# Power.net
KiCad netlist of a schematic drawn in Altium Designer
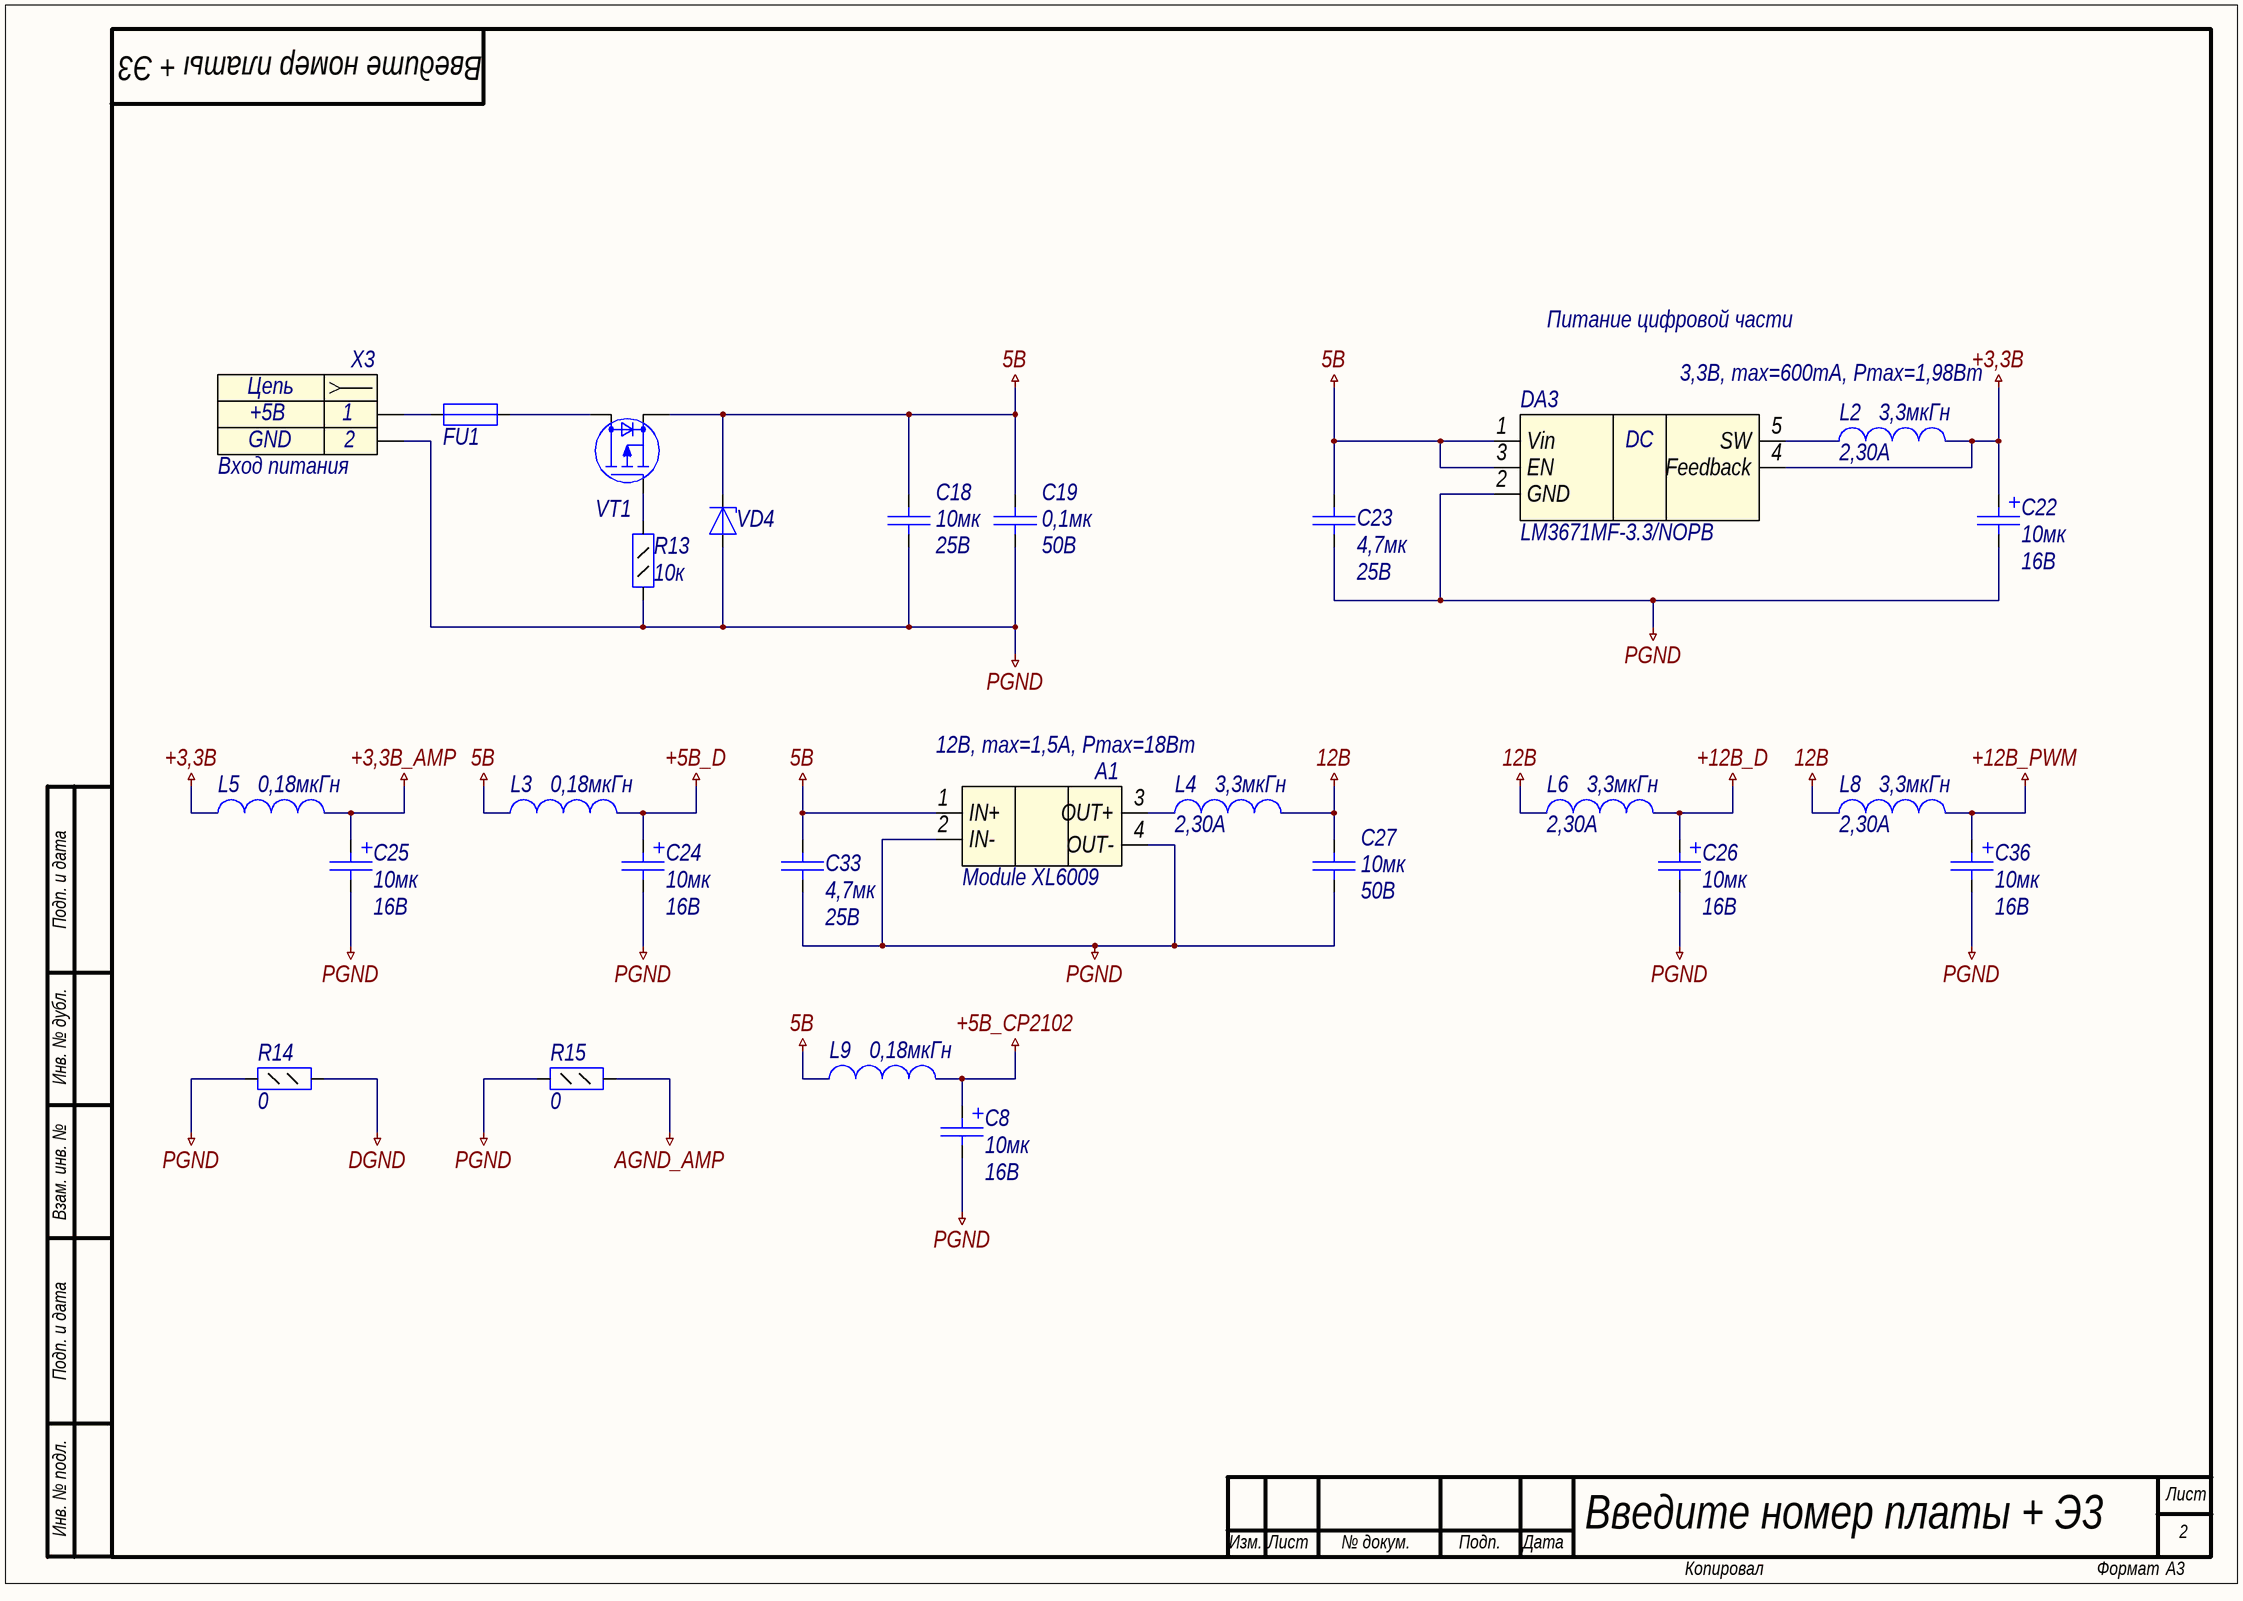
[diagram p0: Power.SchDoc]

(export (version "E")
  (design (tool "Eeschema 10.0.6"))
  (components
    (comp (ref "A1")
      (value "Module XL6009")
      (footprint "Module XL6009")
      (description "DC-DC step-up converter for 5/32-V to 5/35-V")
      (libsource (lib "MOP44") (part "Module XL6009"))
    )
    (comp (ref "C8")
      (value "10мк")
      (footprint "TANTAL CASE A")
      (description "Конденсатор полярный")
      (fields
        (field (name "VOLTAGE") "16В")
        (field (name "PART NUMBER") "293D106X9016A2TE3")
        (field (name "Comment") "Capacitor_pol")
      )
      (libsource (lib "MOP44") (part "Capacitor_pol"))
    )
    (comp (ref "C18")
      (value "10мк")
      (footprint "C1206")
      (description "Конденсатор")
      (fields
        (field (name "VOLTAGE") "25В")
        (field (name "PART NUMBER") "GRM31CR71E106KA12L*")
        (field (name "Comment") "Capacitor")
      )
      (libsource (lib "MOP44") (part "Capacitor"))
    )
    (comp (ref "C19")
      (value "0,1мк")
      (footprint "C0805")
      (description "Конденсатор")
      (fields
        (field (name "VOLTAGE") "50В")
        (field (name "PART NUMBER") "GRM21BR71H104KA01L ")
        (field (name "Comment") "Capacitor")
      )
      (libsource (lib "MOP44") (part "Capacitor"))
    )
    (comp (ref "C22")
      (value "10мк")
      (footprint "TANTAL CASE A")
      (description "Конденсатор полярный")
      (fields
        (field (name "VOLTAGE") "16В")
        (field (name "PART NUMBER") "293D106X9016A2TE3")
        (field (name "Comment") "Capacitor_pol")
      )
      (libsource (lib "MOP44") (part "Capacitor_pol"))
    )
    (comp (ref "C23")
      (value "4,7мк")
      (footprint "C0805")
      (description "Конденсатор")
      (fields
        (field (name "VOLTAGE") "25B")
        (field (name "PART NUMBER") "GRM21BR61E475KA12L")
        (field (name "Comment") "Capacitor")
      )
      (libsource (lib "MOP44") (part "Capacitor"))
    )
    (comp (ref "C24")
      (value "10мк")
      (footprint "TANTAL CASE A")
      (description "Конденсатор полярный")
      (fields
        (field (name "VOLTAGE") "16В")
        (field (name "PART NUMBER") "293D106X9016A2TE3")
        (field (name "Comment") "Capacitor_pol")
      )
      (libsource (lib "MOP44") (part "Capacitor_pol"))
    )
    (comp (ref "C25")
      (value "10мк")
      (footprint "TANTAL CASE A")
      (description "Конденсатор полярный")
      (fields
        (field (name "VOLTAGE") "16В")
        (field (name "PART NUMBER") "293D106X9016A2TE3")
        (field (name "Comment") "Capacitor_pol")
      )
      (libsource (lib "MOP44") (part "Capacitor_pol"))
    )
    (comp (ref "C26")
      (value "10мк")
      (footprint "TANTAL CASE A")
      (description "Конденсатор полярный")
      (fields
        (field (name "VOLTAGE") "16В")
        (field (name "PART NUMBER") "293D106X9016A2TE3")
        (field (name "Comment") "Capacitor_pol")
      )
      (libsource (lib "MOP44") (part "Capacitor_pol"))
    )
    (comp (ref "C27")
      (value "10мк")
      (footprint "C1210")
      (description "Конденсатор")
      (fields
        (field (name "VOLTAGE") "50В")
        (field (name "PART NUMBER") "GRM32ER71H106K")
        (field (name "Comment") "Capacitor")
      )
      (libsource (lib "MOP44") (part "Capacitor"))
    )
    (comp (ref "C33")
      (value "4,7мк")
      (footprint "C0805")
      (description "Конденсатор")
      (fields
        (field (name "VOLTAGE") "25B")
        (field (name "PART NUMBER") "GRM21BR61E475KA12L")
        (field (name "Comment") "Capacitor")
      )
      (libsource (lib "MOP44") (part "Capacitor"))
    )
    (comp (ref "C36")
      (value "10мк")
      (footprint "TANTAL CASE A")
      (description "Конденсатор полярный")
      (fields
        (field (name "VOLTAGE") "16В")
        (field (name "PART NUMBER") "293D106X9016A2TE3")
        (field (name "Comment") "Capacitor_pol")
      )
      (libsource (lib "MOP44") (part "Capacitor_pol"))
    )
    (comp (ref "DA3")
      (value "LM3671MF")
      (footprint "SOT23-5")
      (description "Step-Down DC-DC Converter")
      (fields
        (field (name "PART NUMBER") "LM3671MF-3.3/NOPB")
        (field (name "MANUFACTURER") "Texas Instruments")
      )
      (libsource (lib "MOP44") (part "LM3671MF"))
    )
    (comp (ref "FU1")
      (value "Fuse")
      (footprint "FUSE812")
      (description "Предохранитель")
      (fields (field (name "PART NUMBER") "MF-MSMF075"))
      (libsource (lib "MOP44") (part "Fuse"))
    )
    (comp (ref "L2")
      (value "3,3мкГн")
      (footprint "SRR0604")
      (description "EMI Suppression Filter")
      (fields
        (field (name "RATED CURRENT") "2,30А")
        (field (name "PART NUMBER") "SRR0604-3R3ML")
        (field (name "Comment") "Inductor")
      )
      (libsource (lib "MOP44") (part "Inductor"))
    )
    (comp (ref "L3")
      (value "0,18мкГн")
      (footprint "L0805")
      (description "EMI Suppression Filter")
      (fields (field (name "PART NUMBER") "CM201212-R18KL") (field (name "Comment") "Inductor"))
      (libsource (lib "MOP44") (part "Inductor"))
    )
    (comp (ref "L4")
      (value "3,3мкГн")
      (footprint "SRR0604")
      (description "EMI Suppression Filter")
      (fields
        (field (name "RATED CURRENT") "2,30А")
        (field (name "PART NUMBER") "SRR0604-3R3ML")
        (field (name "Comment") "Inductor")
      )
      (libsource (lib "MOP44") (part "Inductor"))
    )
    (comp (ref "L5")
      (value "0,18мкГн")
      (footprint "L0805")
      (description "EMI Suppression Filter")
      (fields (field (name "PART NUMBER") "CM201212-R18KL") (field (name "Comment") "Inductor"))
      (libsource (lib "MOP44") (part "Inductor"))
    )
    (comp (ref "L6")
      (value "3,3мкГн")
      (footprint "SRR0604")
      (description "EMI Suppression Filter")
      (fields
        (field (name "RATED CURRENT") "2,30А")
        (field (name "PART NUMBER") "SRR0604-3R3ML")
        (field (name "Comment") "Inductor")
      )
      (libsource (lib "MOP44") (part "Inductor"))
    )
    (comp (ref "L8")
      (value "3,3мкГн")
      (footprint "SRR0604")
      (description "EMI Suppression Filter")
      (fields
        (field (name "RATED CURRENT") "2,30А")
        (field (name "PART NUMBER") "SRR0604-3R3ML")
        (field (name "Comment") "Inductor")
      )
      (libsource (lib "MOP44") (part "Inductor"))
    )
    (comp (ref "L9")
      (value "0,18мкГн")
      (footprint "L0805")
      (description "EMI Suppression Filter")
      (fields (field (name "PART NUMBER") "CM201212-R18KL") (field (name "Comment") "Inductor"))
      (libsource (lib "MOP44") (part "Inductor"))
    )
    (comp (ref "R13")
      (value "10к")
      (footprint "R0805")
      (description "Резистор")
      (fields (field (name "PART NUMBER") "RC0805FR-0710KL") (field (name "POWER") "0,125Вт"))
      (libsource (lib "") (part "Resistor_0,125Вт_1"))
    )
    (comp (ref "R14")
      (value "0")
      (footprint "R0805")
      (description "Резистор")
      (fields (field (name "PART NUMBER") "RC0805FR-070RL") (field (name "POWER") "0,125Вт"))
      (libsource (lib "MOP44") (part "Resistor_0,125Вт"))
    )
    (comp (ref "R15")
      (value "0")
      (footprint "R0805")
      (description "Резистор")
      (fields (field (name "PART NUMBER") "RC0805FR-070RL") (field (name "POWER") "0,125Вт"))
      (libsource (lib "MOP44") (part "Resistor_0,125Вт"))
    )
    (comp (ref "VD4")
      (value "DiodeZener")
      (footprint "SMA")
      (description "Cтабилитрон (лавинный выпрямительный диод) односторонний")
      (fields (field (name "PART NUMBER") "SMAJ5.0A"))
      (libsource (lib "MOP44") (part "DiodeZener"))
    )
    (comp (ref "VT1")
      (value "P-MOSFET")
      (footprint "SOT23-3")
      (description "N-MOSFET")
      (fields
        (field (name "PART NUMBER") "IRLML6401TRPBF")
        (field (name "MANUFACTURER") "International Rectifier")
      )
      (libsource (lib "MOP44") (part "P-MOSFET"))
    )
    (comp (ref "X3")
      (value "Вход питания")
      (footprint "CWF-2R")
      (description "Разъем - 2 конт. розетка")
      (fields (field (name "PART NUMBER") "DS1069-2 MR-A"))
      (libsource (lib "MOP44") (part "Header_2_sct"))
    )
  )
  (nets
    (net (code "1") (name "+3,3В") (class "Default")
      (node (ref "C22") (pin "1") (pinfunction "1_1") (pintype "passive"))
      (node (ref "DA3") (pin "4") (pinfunction "Feedback_4") (pintype "power_in"))
      (node (ref "L2") (pin "2") (pinfunction "2_2") (pintype "passive"))
      (node (ref "L5") (pin "1") (pinfunction "1_1") (pintype "passive"))
    )
    (net (code "2") (name "+3,3В_AMP") (class "Default")
      (node (ref "C25") (pin "1") (pinfunction "1_1") (pintype "passive"))
      (node (ref "L5") (pin "2") (pinfunction "2_2") (pintype "passive"))
    )
    (net (code "3") (name "+5B_CP2102") (class "Default")
      (node (ref "C8") (pin "1") (pinfunction "1_1") (pintype "passive"))
      (node (ref "L9") (pin "2") (pinfunction "2_2") (pintype "passive"))
    )
    (net (code "4") (name "+5B_D") (class "Default")
      (node (ref "C24") (pin "1") (pinfunction "1_1") (pintype "passive"))
      (node (ref "L3") (pin "2") (pinfunction "2_2") (pintype "passive"))
    )
    (net (code "5") (name "+12В_D") (class "Default")
      (node (ref "C26") (pin "1") (pinfunction "1_1") (pintype "passive"))
      (node (ref "L6") (pin "2") (pinfunction "2_2") (pintype "passive"))
    )
    (net (code "6") (name "+12В_PWM") (class "Default")
      (node (ref "C36") (pin "1") (pinfunction "1_1") (pintype "passive"))
      (node (ref "L8") (pin "2") (pinfunction "2_2") (pintype "passive"))
    )
    (net (code "7") (name "5B") (class "Default")
      (node (ref "A1") (pin "1") (pinfunction "IN+_1") (pintype "power_in"))
      (node (ref "C18") (pin "2") (pinfunction "2_2") (pintype "passive"))
      (node (ref "C19") (pin "2") (pinfunction "2_2") (pintype "passive"))
      (node (ref "C23") (pin "2") (pinfunction "2_2") (pintype "passive"))
      (node (ref "C33") (pin "2") (pinfunction "2_2") (pintype "passive"))
      (node (ref "DA3") (pin "1") (pinfunction "Vin_1") (pintype "power_in"))
      (node (ref "DA3") (pin "3") (pinfunction "EN_3") (pintype "power_in"))
      (node (ref "L3") (pin "1") (pinfunction "1_1") (pintype "passive"))
      (node (ref "L9") (pin "1") (pinfunction "1_1") (pintype "passive"))
      (node (ref "VD4") (pin "1") (pinfunction "K_1") (pintype "passive"))
      (node (ref "VT1") (pin "3") (pinfunction "S_3") (pintype "passive"))
    )
    (net (code "8") (name "12В") (class "Default")
      (node (ref "C27") (pin "2") (pinfunction "2_2") (pintype "passive"))
      (node (ref "L4") (pin "2") (pinfunction "2_2") (pintype "passive"))
      (node (ref "L6") (pin "1") (pinfunction "1_1") (pintype "passive"))
      (node (ref "L8") (pin "1") (pinfunction "1_1") (pintype "passive"))
    )
    (net (code "9") (name "AGND_AMP") (class "Default")
      (node (ref "R15") (pin "2") (pinfunction "2_2") (pintype "passive"))
    )
    (net (code "10") (name "DGND") (class "Default")
      (node (ref "R14") (pin "2") (pinfunction "2_2") (pintype "passive"))
    )
    (net (code "11") (name "Net-(A1-OUT+)") (class "Default")
      (node (ref "A1") (pin "3") (pinfunction "OUT+_3") (pintype "power_in"))
      (node (ref "L4") (pin "1") (pinfunction "1_1") (pintype "passive"))
    )
    (net (code "12") (name "Net-(DA3-SW)") (class "Default")
      (node (ref "DA3") (pin "5") (pinfunction "SW_5") (pintype "power_in"))
      (node (ref "L2") (pin "1") (pinfunction "1_1") (pintype "passive"))
    )
    (net (code "13") (name "Net-(FU1-Pad1)") (class "Default")
      (node (ref "FU1") (pin "1") (pinfunction "1_1") (pintype "passive"))
      (node (ref "X3") (pin "1") (pinfunction "1_1") (pintype "passive"))
    )
    (net (code "14") (name "Net-(VT1-D)") (class "Default")
      (node (ref "FU1") (pin "2") (pinfunction "2_2") (pintype "passive"))
      (node (ref "VT1") (pin "2") (pinfunction "D_2") (pintype "passive"))
    )
    (net (code "15") (name "Net-(VT1-G)") (class "Default")
      (node (ref "R13") (pin "2") (pinfunction "2_2") (pintype "passive"))
      (node (ref "VT1") (pin "1") (pinfunction "G_1") (pintype "passive"))
    )
    (net (code "16") (name "PGND") (class "Default")
      (node (ref "A1") (pin "2") (pinfunction "IN-_2") (pintype "power_in"))
      (node (ref "A1") (pin "4") (pinfunction "OUT-_4") (pintype "power_in"))
      (node (ref "C18") (pin "1") (pinfunction "1_1") (pintype "passive"))
      (node (ref "C19") (pin "1") (pinfunction "1_1") (pintype "passive"))
      (node (ref "C22") (pin "2") (pinfunction "2_2") (pintype "passive"))
      (node (ref "C23") (pin "1") (pinfunction "1_1") (pintype "passive"))
      (node (ref "C24") (pin "2") (pinfunction "2_2") (pintype "passive"))
      (node (ref "C25") (pin "2") (pinfunction "2_2") (pintype "passive"))
      (node (ref "C26") (pin "2") (pinfunction "2_2") (pintype "passive"))
      (node (ref "C27") (pin "1") (pinfunction "1_1") (pintype "passive"))
      (node (ref "C33") (pin "1") (pinfunction "1_1") (pintype "passive"))
      (node (ref "C36") (pin "2") (pinfunction "2_2") (pintype "passive"))
      (node (ref "C8") (pin "2") (pinfunction "2_2") (pintype "passive"))
      (node (ref "DA3") (pin "2") (pinfunction "GND_2") (pintype "power_in"))
      (node (ref "R13") (pin "1") (pinfunction "1_1") (pintype "passive"))
      (node (ref "R14") (pin "1") (pinfunction "1_1") (pintype "passive"))
      (node (ref "R15") (pin "1") (pinfunction "1_1") (pintype "passive"))
      (node (ref "VD4") (pin "2") (pinfunction "A_2") (pintype "passive"))
      (node (ref "X3") (pin "2") (pinfunction "2_2") (pintype "passive"))
    )
  )
)
